# Motor.net
KiCad netlist of a schematic drawn in EAGLE
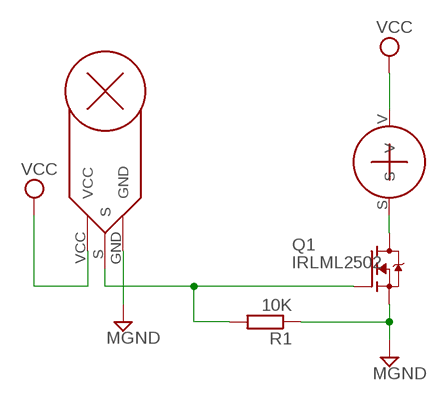
[diagram p0: schematic, sheet 1]

(export (version "E")
  (design (tool "Eeschema 10.0.6"))
  (components
    (comp (ref "Q1")
      (value "IRLML2502")
      (footprint "eagle-import:SOT23-3")
      (libsource (lib "eagle-import") (part "IRLML2502"))
    )
    (comp (ref "R1")
      (value "10K")
      (footprint "eagle-import:R0805")
      (libsource (lib "eagle-import") (part "R-EU_R0805"))
    )
    (comp (ref "U$1")
      (value "MOTOR")
      (footprint "eagle-import:MOTOR")
      (libsource (lib "eagle-import") (part "MOTOR"))
    )
    (comp (ref "U$2")
      (value "MOTOR-BOARDBOARD")
      (footprint "eagle-import:MOTOR-BOARD")
      (libsource (lib "eagle-import") (part "MOTOR-BOARDBOARD"))
    )
  )
  (nets
    (net (code "1") (name "MGND") (class "Default")
      (node (ref "Q1") (pin "2") (pinfunction "S_2") (pintype "passive"))
      (node (ref "R1") (pin "1") (pinfunction "1_1") (pintype "passive"))
      (node (ref "U$2") (pin "GND") (pinfunction "GND_GND") (pintype "bidirectional"))
    )
    (net (code "2") (name "Net-(Q1-D)") (class "Default")
      (node (ref "Q1") (pin "3") (pinfunction "D_3") (pintype "passive"))
      (node (ref "U$1") (pin "S") (pinfunction "S_S") (pintype "bidirectional"))
    )
    (net (code "3") (name "Net-(Q1-G)") (class "Default")
      (node (ref "Q1") (pin "1") (pinfunction "G_1") (pintype "passive"))
      (node (ref "R1") (pin "2") (pinfunction "2_2") (pintype "passive"))
      (node (ref "U$2") (pin "S") (pinfunction "S_S") (pintype "bidirectional"))
    )
    (net (code "4") (name "VCC") (class "Default")
      (node (ref "U$1") (pin "V") (pinfunction "V_V") (pintype "bidirectional"))
      (node (ref "U$2") (pin "VCC") (pinfunction "VCC_VCC") (pintype "bidirectional"))
    )
  )
)
